# VME_buffers.net
KiCad netlist of a schematic drawn in Altium Designer
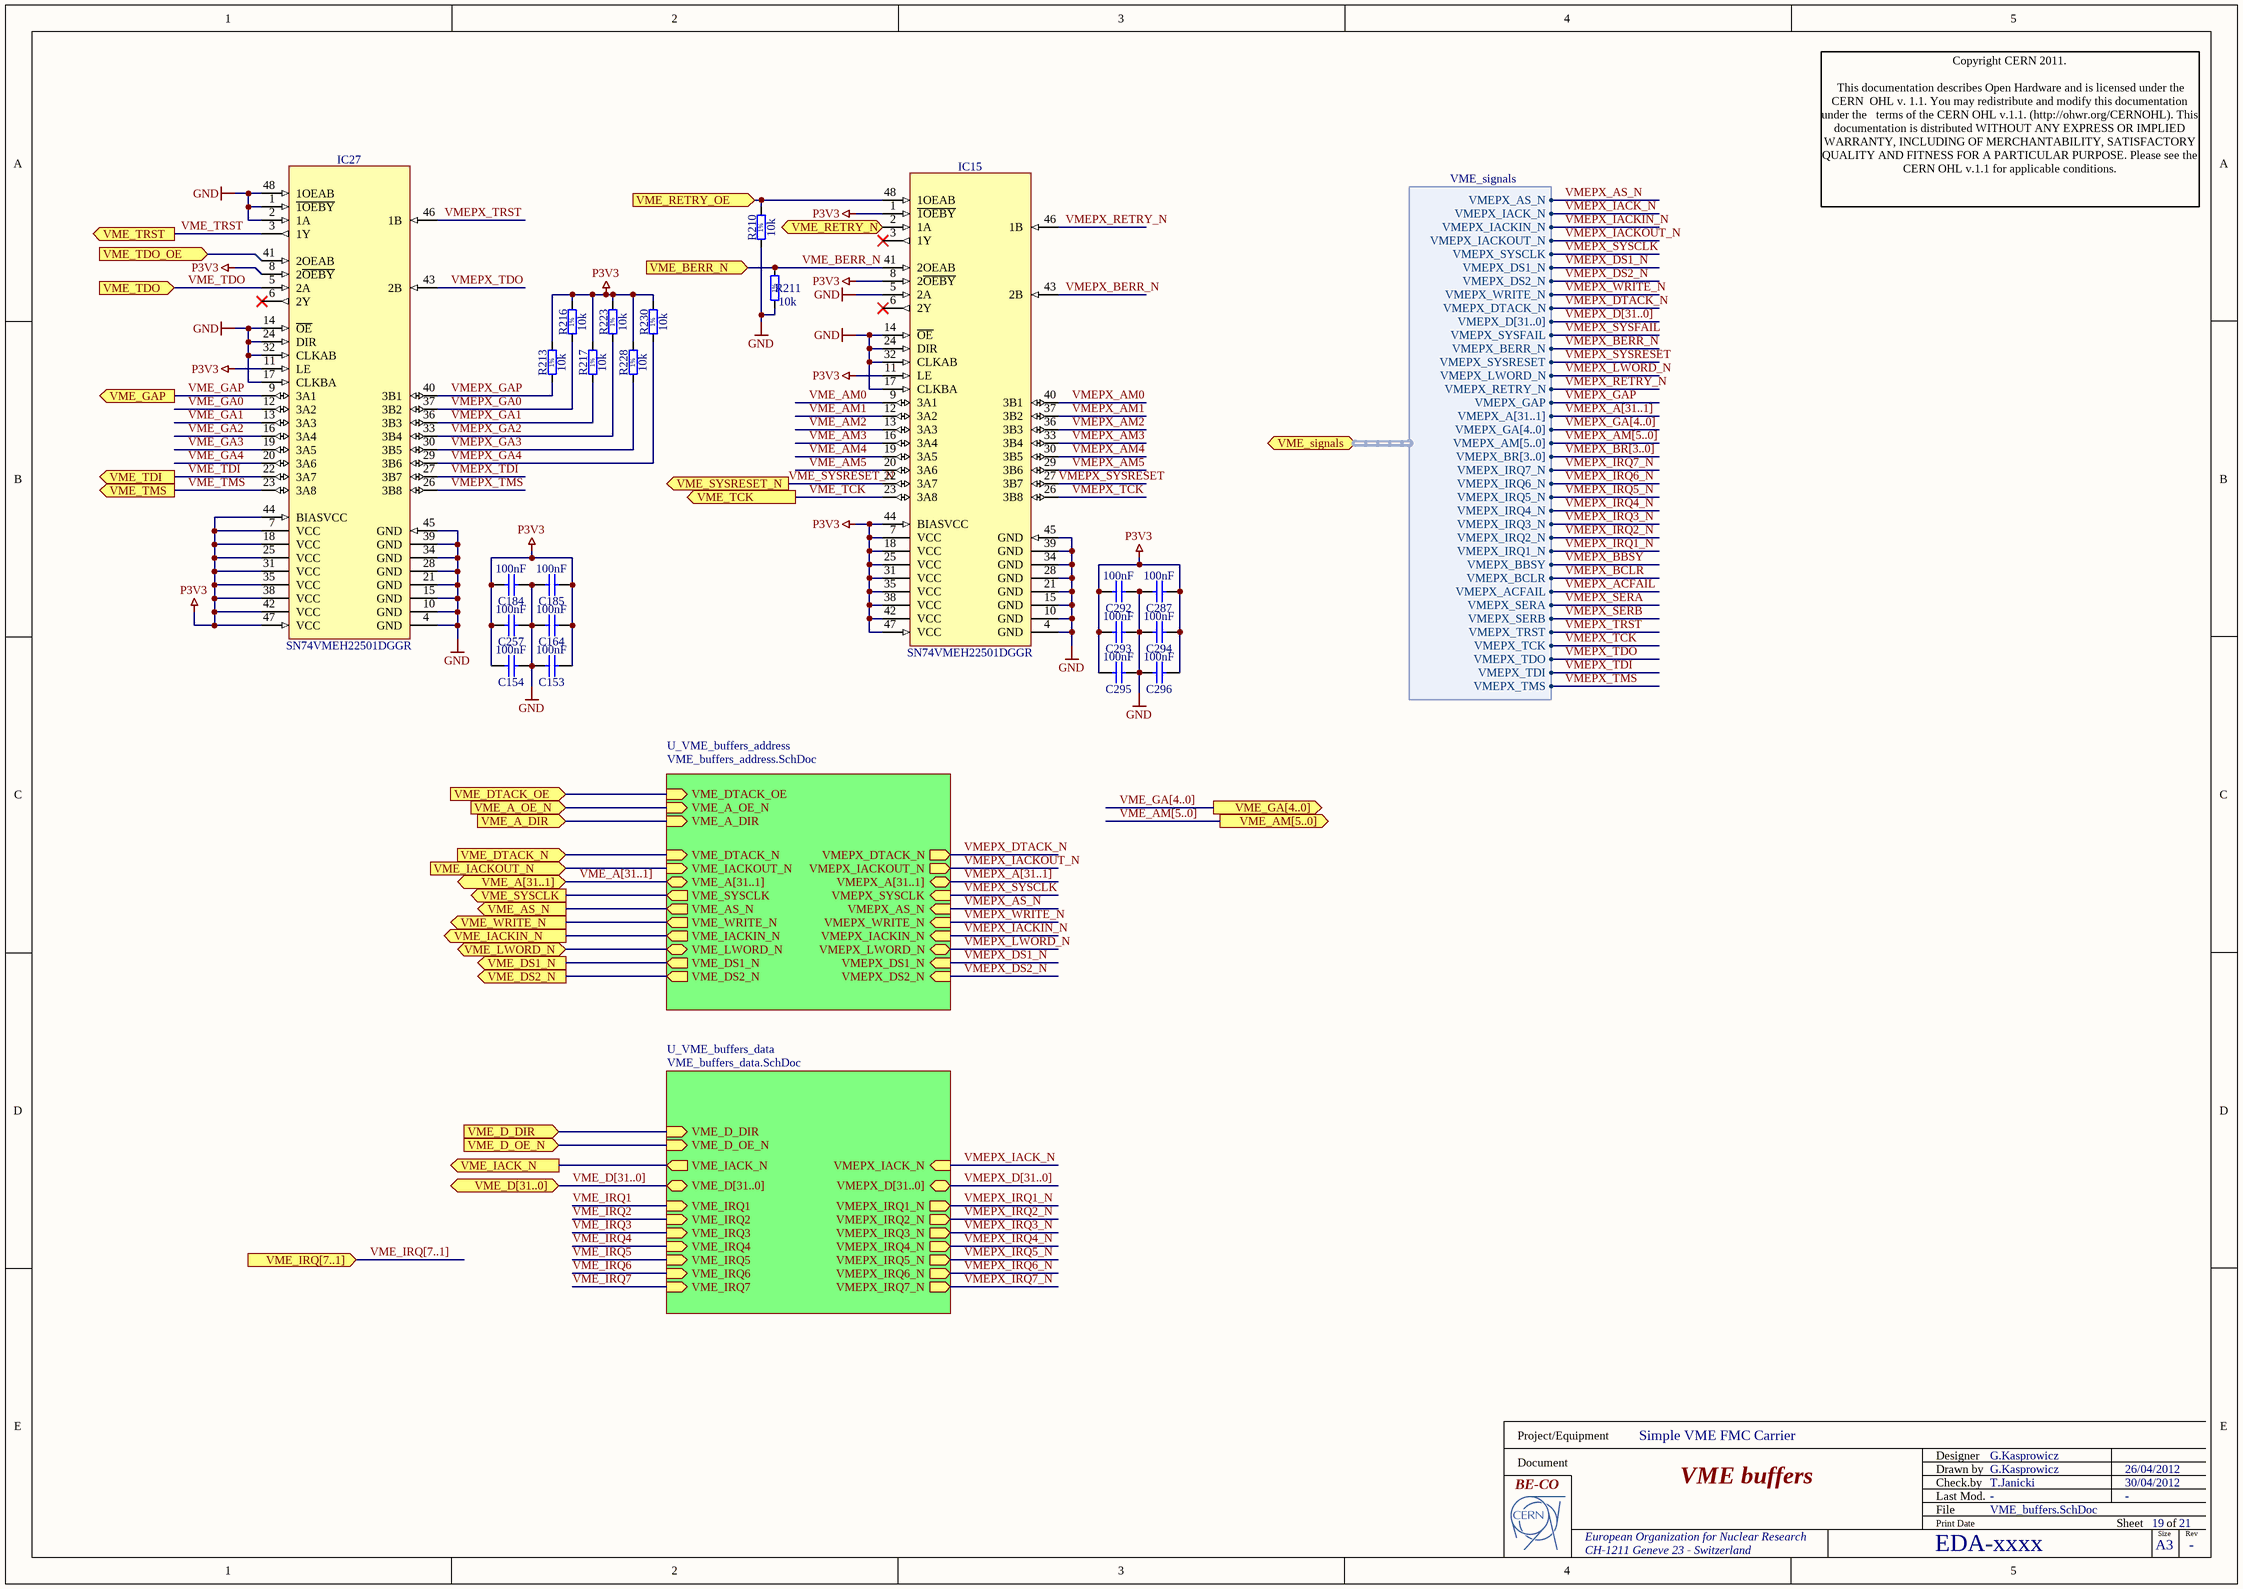
[diagram p0: VME_buffers.SchDoc]

(export (version "E")
  (design (tool "Eeschema 10.0.6"))
  (components
    (comp (ref "C153")
      (value "100nF")
      (footprint "CAPC1005X55N")
      (description "Non-polarised capacitor")
      (fields
        (field (name "PART NUMBER") "CC0402_100NF_16V_10%_X7R")
        (field (name "VOLTAGE") "16V")
        (field (name "AUTHOR") "CERN DEM JLC")
      )
      (libsource (lib "Capacitors") (part "Capacitor - non polarized"))
    )
    (comp (ref "C154")
      (value "100nF")
      (footprint "CAPC1005X55N")
      (description "Non-polarised capacitor")
      (fields
        (field (name "PART NUMBER") "CC0402_100NF_16V_10%_X7R")
        (field (name "VOLTAGE") "16V")
        (field (name "AUTHOR") "CERN DEM JLC")
      )
      (libsource (lib "Capacitors") (part "Capacitor - non polarized"))
    )
    (comp (ref "C164")
      (value "100nF")
      (footprint "CAPC1005X55N")
      (description "Non-polarised capacitor")
      (fields
        (field (name "PART NUMBER") "CC0402_100NF_16V_10%_X7R")
        (field (name "VOLTAGE") "16V")
        (field (name "AUTHOR") "CERN DEM JLC")
      )
      (libsource (lib "Capacitors") (part "Capacitor - non polarized"))
    )
    (comp (ref "C184")
      (value "100nF")
      (footprint "CAPC1005X55N")
      (description "Non-polarised capacitor")
      (fields
        (field (name "PART NUMBER") "CC0402_100NF_16V_10%_X7R")
        (field (name "VOLTAGE") "16V")
        (field (name "AUTHOR") "CERN DEM JLC")
      )
      (libsource (lib "Capacitors") (part "Capacitor - non polarized"))
    )
    (comp (ref "C185")
      (value "100nF")
      (footprint "CAPC1005X55N")
      (description "Non-polarised capacitor")
      (fields
        (field (name "PART NUMBER") "CC0402_100NF_16V_10%_X7R")
        (field (name "VOLTAGE") "16V")
        (field (name "AUTHOR") "CERN DEM JLC")
      )
      (libsource (lib "Capacitors") (part "Capacitor - non polarized"))
    )
    (comp (ref "C257")
      (value "100nF")
      (footprint "CAPC1005X55N")
      (description "Non-polarised capacitor")
      (fields
        (field (name "PART NUMBER") "CC0402_100NF_16V_10%_X7R")
        (field (name "VOLTAGE") "16V")
        (field (name "AUTHOR") "CERN DEM JLC")
      )
      (libsource (lib "Capacitors") (part "Capacitor - non polarized"))
    )
    (comp (ref "C287")
      (value "100nF")
      (footprint "CAPC1005X55N")
      (description "Non-polarised capacitor")
      (fields
        (field (name "PART NUMBER") "CC0402_100NF_16V_10%_X7R")
        (field (name "VOLTAGE") "16V")
        (field (name "AUTHOR") "CERN DEM JLC")
      )
      (libsource (lib "Capacitors") (part "Capacitor - non polarized"))
    )
    (comp (ref "C292")
      (value "100nF")
      (footprint "CAPC1005X55N")
      (description "Non-polarised capacitor")
      (fields
        (field (name "PART NUMBER") "CC0402_100NF_16V_10%_X7R")
        (field (name "VOLTAGE") "16V")
        (field (name "AUTHOR") "CERN DEM JLC")
      )
      (libsource (lib "Capacitors") (part "Capacitor - non polarized"))
    )
    (comp (ref "C293")
      (value "100nF")
      (footprint "CAPC1005X55N")
      (description "Non-polarised capacitor")
      (fields
        (field (name "PART NUMBER") "CC0402_100NF_16V_10%_X7R")
        (field (name "VOLTAGE") "16V")
        (field (name "AUTHOR") "CERN DEM JLC")
      )
      (libsource (lib "Capacitors") (part "Capacitor - non polarized"))
    )
    (comp (ref "C294")
      (value "100nF")
      (footprint "CAPC1005X55N")
      (description "Non-polarised capacitor")
      (fields
        (field (name "PART NUMBER") "CC0402_100NF_16V_10%_X7R")
        (field (name "VOLTAGE") "16V")
        (field (name "AUTHOR") "CERN DEM JLC")
      )
      (libsource (lib "Capacitors") (part "Capacitor - non polarized"))
    )
    (comp (ref "C295")
      (value "100nF")
      (footprint "CAPC1005X55N")
      (description "Non-polarised capacitor")
      (fields
        (field (name "PART NUMBER") "CC0402_100NF_16V_10%_X7R")
        (field (name "VOLTAGE") "16V")
        (field (name "AUTHOR") "CERN DEM JLC")
      )
      (libsource (lib "Capacitors") (part "Capacitor - non polarized"))
    )
    (comp (ref "C296")
      (value "100nF")
      (footprint "CAPC1005X55N")
      (description "Non-polarised capacitor")
      (fields
        (field (name "PART NUMBER") "CC0402_100NF_16V_10%_X7R")
        (field (name "VOLTAGE") "16V")
        (field (name "AUTHOR") "CERN DEM JLC")
      )
      (libsource (lib "Capacitors") (part "Capacitor - non polarized"))
    )
    (comp (ref "IC15")
      (value "SN74VMEH22501DGGR")
      (footprint "SOP50P810X120-48N")
      (description "8-Bit Universal Bus Transceiver and Two 1-Bit Bus Transceivers with 3-State Outputs")
      (fields (field (name "MANUFACTURER") "TEXAS INSTRUMENTS") (field (name "AUTHOR") "CERN DEM JLC"))
      (libsource (lib "ICs And Semiconductors") (part "74VMEH22501"))
    )
    (comp (ref "IC27")
      (value "SN74VMEH22501DGGR")
      (footprint "SOP50P810X120-48N")
      (description "8-Bit Universal Bus Transceiver and Two 1-Bit Bus Transceivers with 3-State Outputs")
      (fields (field (name "MANUFACTURER") "TEXAS INSTRUMENTS") (field (name "AUTHOR") "CERN DEM JLC"))
      (libsource (lib "ICs And Semiconductors") (part "74VMEH22501"))
    )
    (comp (ref "R210")
      (value "10k")
      (footprint "RESC1608X55N")
      (description "Resistor - 1%")
      (fields
        (field (name "PART NUMBER") "R0603_10K_1%_0.1W_100PPM")
        (field (name "POWER") "0.1W")
        (field (name "AUTHOR") "CERN DEM JLC")
      )
      (libsource (lib "Resistors") (part "Resistor - 1%"))
    )
    (comp (ref "R211")
      (value "10k")
      (footprint "RESC1608X55N")
      (description "Resistor - 1%")
      (fields
        (field (name "PART NUMBER") "R0603_10K_1%_0.1W_100PPM")
        (field (name "POWER") "0.1W")
        (field (name "AUTHOR") "CERN DEM JLC")
      )
      (libsource (lib "Resistors") (part "Resistor - 1%"))
    )
    (comp (ref "R213")
      (value "10k")
      (footprint "RESC1608X55N")
      (description "Resistor - 1%")
      (fields
        (field (name "PART NUMBER") "R0603_10K_1%_0.1W_100PPM")
        (field (name "POWER") "0.1W")
        (field (name "AUTHOR") "CERN DEM JLC")
      )
      (libsource (lib "Resistors") (part "Resistor - 1%"))
    )
    (comp (ref "R216")
      (value "10k")
      (footprint "RESC1608X55N")
      (description "Resistor - 1%")
      (fields
        (field (name "PART NUMBER") "R0603_10K_1%_0.1W_100PPM")
        (field (name "POWER") "0.1W")
        (field (name "AUTHOR") "CERN DEM JLC")
      )
      (libsource (lib "Resistors") (part "Resistor - 1%"))
    )
    (comp (ref "R217")
      (value "10k")
      (footprint "RESC1608X55N")
      (description "Resistor - 1%")
      (fields
        (field (name "PART NUMBER") "R0603_10K_1%_0.1W_100PPM")
        (field (name "POWER") "0.1W")
        (field (name "AUTHOR") "CERN DEM JLC")
      )
      (libsource (lib "Resistors") (part "Resistor - 1%"))
    )
    (comp (ref "R223")
      (value "10k")
      (footprint "RESC1608X55N")
      (description "Resistor - 1%")
      (fields
        (field (name "PART NUMBER") "R0603_10K_1%_0.1W_100PPM")
        (field (name "POWER") "0.1W")
        (field (name "AUTHOR") "CERN DEM JLC")
      )
      (libsource (lib "Resistors") (part "Resistor - 1%"))
    )
    (comp (ref "R228")
      (value "10k")
      (footprint "RESC1608X55N")
      (description "Resistor - 1%")
      (fields
        (field (name "PART NUMBER") "R0603_10K_1%_0.1W_100PPM")
        (field (name "POWER") "0.1W")
        (field (name "AUTHOR") "CERN DEM JLC")
      )
      (libsource (lib "Resistors") (part "Resistor - 1%"))
    )
    (comp (ref "R230")
      (value "10k")
      (footprint "RESC1608X55N")
      (description "Resistor - 1%")
      (fields
        (field (name "PART NUMBER") "R0603_10K_1%_0.1W_100PPM")
        (field (name "POWER") "0.1W")
        (field (name "AUTHOR") "CERN DEM JLC")
      )
      (libsource (lib "Resistors") (part "Resistor - 1%"))
    )
  )
  (nets
    (net (code "129") (name "/VMEPX_AM0") (class "Default")
      (node (ref "IC15") (pin "40") (pinfunction "3B1_40") (pintype "bidirectional"))
    )
    (net (code "130") (name "/VMEPX_AM1") (class "Default")
      (node (ref "IC15") (pin "37") (pinfunction "3B2_37") (pintype "bidirectional"))
    )
    (net (code "131") (name "/VMEPX_AM2") (class "Default")
      (node (ref "IC15") (pin "36") (pinfunction "3B3_36") (pintype "bidirectional"))
    )
    (net (code "132") (name "/VMEPX_AM3") (class "Default")
      (node (ref "IC15") (pin "33") (pinfunction "3B4_33") (pintype "bidirectional"))
    )
    (net (code "133") (name "/VMEPX_AM4") (class "Default")
      (node (ref "IC15") (pin "30") (pinfunction "3B5_30") (pintype "bidirectional"))
    )
    (net (code "134") (name "/VMEPX_AM5") (class "Default")
      (node (ref "IC15") (pin "29") (pinfunction "3B6_29") (pintype "bidirectional"))
    )
    (net (code "140") (name "/VMEPX_BERR_N") (class "Default")
      (node (ref "IC15") (pin "43") (pinfunction "2B_43") (pintype "input"))
    )
    (net (code "145") (name "/VMEPX_GA0") (class "Default")
      (node (ref "IC27") (pin "37") (pinfunction "3B2_37") (pintype "bidirectional"))
      (node (ref "R216") (pin "1") (pinfunction "1_1") (pintype "passive"))
    )
    (net (code "146") (name "/VMEPX_GA1") (class "Default")
      (node (ref "IC27") (pin "36") (pinfunction "3B3_36") (pintype "bidirectional"))
      (node (ref "R217") (pin "1") (pinfunction "1_1") (pintype "passive"))
    )
    (net (code "147") (name "/VMEPX_GA2") (class "Default")
      (node (ref "IC27") (pin "33") (pinfunction "3B4_33") (pintype "bidirectional"))
      (node (ref "R223") (pin "1") (pinfunction "1_1") (pintype "passive"))
    )
    (net (code "148") (name "/VMEPX_GA3") (class "Default")
      (node (ref "IC27") (pin "30") (pinfunction "3B5_30") (pintype "bidirectional"))
      (node (ref "R228") (pin "1") (pinfunction "1_1") (pintype "passive"))
    )
    (net (code "149") (name "/VMEPX_GA4") (class "Default")
      (node (ref "IC27") (pin "29") (pinfunction "3B6_29") (pintype "bidirectional"))
      (node (ref "R230") (pin "1") (pinfunction "1_1") (pintype "passive"))
    )
    (net (code "150") (name "/VMEPX_GAP") (class "Default")
      (node (ref "IC27") (pin "40") (pinfunction "3B1_40") (pintype "bidirectional"))
      (node (ref "R213") (pin "1") (pinfunction "1_1") (pintype "passive"))
    )
    (net (code "163") (name "/VMEPX_RETRY_N") (class "Default")
      (node (ref "IC15") (pin "46") (pinfunction "1B_46") (pintype "input"))
    )
    (net (code "168") (name "/VMEPX_SYSRESET") (class "Default")
      (node (ref "IC15") (pin "27") (pinfunction "3B7_27") (pintype "bidirectional"))
    )
    (net (code "169") (name "/VMEPX_TCK") (class "Default")
      (node (ref "IC15") (pin "26") (pinfunction "3B8_26") (pintype "bidirectional"))
    )
    (net (code "170") (name "/VMEPX_TDI") (class "Default")
      (node (ref "IC27") (pin "27") (pinfunction "3B7_27") (pintype "bidirectional"))
    )
    (net (code "171") (name "/VMEPX_TDO") (class "Default")
      (node (ref "IC27") (pin "43") (pinfunction "2B_43") (pintype "input"))
    )
    (net (code "172") (name "/VMEPX_TMS") (class "Default")
      (node (ref "IC27") (pin "26") (pinfunction "3B8_26") (pintype "bidirectional"))
    )
    (net (code "173") (name "/VMEPX_TRST") (class "Default")
      (node (ref "IC27") (pin "46") (pinfunction "1B_46") (pintype "input"))
    )
    (net (code "175") (name "/VME_AM0") (class "Default")
      (node (ref "IC15") (pin "9") (pinfunction "3A1_9") (pintype "bidirectional"))
    )
    (net (code "176") (name "/VME_AM1") (class "Default")
      (node (ref "IC15") (pin "12") (pinfunction "3A2_12") (pintype "bidirectional"))
    )
    (net (code "177") (name "/VME_AM2") (class "Default")
      (node (ref "IC15") (pin "13") (pinfunction "3A3_13") (pintype "bidirectional"))
    )
    (net (code "178") (name "/VME_AM3") (class "Default")
      (node (ref "IC15") (pin "16") (pinfunction "3A4_16") (pintype "bidirectional"))
    )
    (net (code "179") (name "/VME_AM4") (class "Default")
      (node (ref "IC15") (pin "19") (pinfunction "3A5_19") (pintype "bidirectional"))
    )
    (net (code "180") (name "/VME_AM5") (class "Default")
      (node (ref "IC15") (pin "20") (pinfunction "3A6_20") (pintype "bidirectional"))
    )
    (net (code "186") (name "/VME_BERR_N") (class "Default")
      (node (ref "IC15") (pin "41") (pinfunction "2OEAB_41") (pintype "input"))
      (node (ref "R211") (pin "2") (pinfunction "2_2") (pintype "passive"))
    )
    (net (code "194") (name "/VME_GA0") (class "Default")
      (node (ref "IC27") (pin "12") (pinfunction "3A2_12") (pintype "bidirectional"))
    )
    (net (code "195") (name "/VME_GA1") (class "Default")
      (node (ref "IC27") (pin "13") (pinfunction "3A3_13") (pintype "bidirectional"))
    )
    (net (code "196") (name "/VME_GA2") (class "Default")
      (node (ref "IC27") (pin "16") (pinfunction "3A4_16") (pintype "bidirectional"))
    )
    (net (code "197") (name "/VME_GA3") (class "Default")
      (node (ref "IC27") (pin "19") (pinfunction "3A5_19") (pintype "bidirectional"))
    )
    (net (code "198") (name "/VME_GA4") (class "Default")
      (node (ref "IC27") (pin "20") (pinfunction "3A6_20") (pintype "bidirectional"))
    )
    (net (code "199") (name "/VME_GAP") (class "Default")
      (node (ref "IC27") (pin "9") (pinfunction "3A1_9") (pintype "bidirectional"))
    )
    (net (code "213") (name "/VME_RETRY_N") (class "Default")
      (node (ref "IC15") (pin "2") (pinfunction "1A_2") (pintype "input"))
    )
    (net (code "214") (name "/VME_RETRY_OE") (class "Default")
      (node (ref "IC15") (pin "48") (pinfunction "1OEAB_48") (pintype "input"))
      (node (ref "R210") (pin "2") (pinfunction "2_2") (pintype "passive"))
    )
    (net (code "216") (name "/VME_SYSRESET_N") (class "Default")
      (node (ref "IC15") (pin "22") (pinfunction "3A7_22") (pintype "bidirectional"))
    )
    (net (code "217") (name "/VME_TCK") (class "Default")
      (node (ref "IC15") (pin "23") (pinfunction "3A8_23") (pintype "bidirectional"))
    )
    (net (code "218") (name "/VME_TDI") (class "Default")
      (node (ref "IC27") (pin "22") (pinfunction "3A7_22") (pintype "bidirectional"))
    )
    (net (code "219") (name "/VME_TDO") (class "Default")
      (node (ref "IC27") (pin "5") (pinfunction "2A_5") (pintype "input"))
    )
    (net (code "220") (name "/VME_TDO_OE") (class "Default")
      (node (ref "IC27") (pin "41") (pinfunction "2OEAB_41") (pintype "input"))
    )
    (net (code "221") (name "/VME_TMS") (class "Default")
      (node (ref "IC27") (pin "23") (pinfunction "3A8_23") (pintype "bidirectional"))
    )
    (net (code "222") (name "/VME_TRST") (class "Default")
      (node (ref "IC27") (pin "3") (pinfunction "1Y_3") (pintype "output"))
    )
    (net (code "226") (name "GND") (class "Default")
      (node (ref "C153") (pin "2") (pinfunction "2_2") (pintype "passive"))
      (node (ref "C154") (pin "1") (pinfunction "1_1") (pintype "passive"))
      (node (ref "C164") (pin "2") (pinfunction "2_2") (pintype "passive"))
      (node (ref "C184") (pin "1") (pinfunction "1_1") (pintype "passive"))
      (node (ref "C185") (pin "2") (pinfunction "2_2") (pintype "passive"))
      (node (ref "C257") (pin "1") (pinfunction "1_1") (pintype "passive"))
      (node (ref "C287") (pin "2") (pinfunction "2_2") (pintype "passive"))
      (node (ref "C292") (pin "1") (pinfunction "1_1") (pintype "passive"))
      (node (ref "C293") (pin "1") (pinfunction "1_1") (pintype "passive"))
      (node (ref "C294") (pin "2") (pinfunction "2_2") (pintype "passive"))
      (node (ref "C295") (pin "1") (pinfunction "1_1") (pintype "passive"))
      (node (ref "C296") (pin "2") (pinfunction "2_2") (pintype "passive"))
      (node (ref "IC15") (pin "10") (pinfunction "GND_10") (pintype "power_in"))
      (node (ref "IC15") (pin "14") (pinfunction "~{OE}_14") (pintype "input"))
      (node (ref "IC15") (pin "15") (pinfunction "GND_15") (pintype "power_in"))
      (node (ref "IC15") (pin "17") (pinfunction "CLKBA_17") (pintype "input"))
      (node (ref "IC15") (pin "21") (pinfunction "GND_21") (pintype "power_in"))
      (node (ref "IC15") (pin "24") (pinfunction "DIR_24") (pintype "input"))
      (node (ref "IC15") (pin "28") (pinfunction "GND_28") (pintype "power_in"))
      (node (ref "IC15") (pin "32") (pinfunction "CLKAB_32") (pintype "input"))
      (node (ref "IC15") (pin "34") (pinfunction "GND_34") (pintype "power_in"))
      (node (ref "IC15") (pin "39") (pinfunction "GND_39") (pintype "power_in"))
      (node (ref "IC15") (pin "4") (pinfunction "GND_4") (pintype "power_in"))
      (node (ref "IC15") (pin "45") (pinfunction "GND_45") (pintype "input"))
      (node (ref "IC15") (pin "5") (pinfunction "2A_5") (pintype "input"))
      (node (ref "IC27") (pin "1") (pinfunction "~{1OEBY}_1") (pintype "input"))
      (node (ref "IC27") (pin "10") (pinfunction "GND_10") (pintype "power_in"))
      (node (ref "IC27") (pin "14") (pinfunction "~{OE}_14") (pintype "input"))
      (node (ref "IC27") (pin "15") (pinfunction "GND_15") (pintype "power_in"))
      (node (ref "IC27") (pin "17") (pinfunction "CLKBA_17") (pintype "input"))
      (node (ref "IC27") (pin "2") (pinfunction "1A_2") (pintype "input"))
      (node (ref "IC27") (pin "21") (pinfunction "GND_21") (pintype "power_in"))
      (node (ref "IC27") (pin "24") (pinfunction "DIR_24") (pintype "input"))
      (node (ref "IC27") (pin "28") (pinfunction "GND_28") (pintype "power_in"))
      (node (ref "IC27") (pin "32") (pinfunction "CLKAB_32") (pintype "input"))
      (node (ref "IC27") (pin "34") (pinfunction "GND_34") (pintype "power_in"))
      (node (ref "IC27") (pin "39") (pinfunction "GND_39") (pintype "power_in"))
      (node (ref "IC27") (pin "4") (pinfunction "GND_4") (pintype "power_in"))
      (node (ref "IC27") (pin "45") (pinfunction "GND_45") (pintype "input"))
      (node (ref "IC27") (pin "48") (pinfunction "1OEAB_48") (pintype "input"))
      (node (ref "R210") (pin "1") (pinfunction "1_1") (pintype "passive"))
      (node (ref "R211") (pin "1") (pinfunction "1_1") (pintype "passive"))
    )
    (net (code "227") (name "P3V3") (class "Default")
      (node (ref "C153") (pin "1") (pinfunction "1_1") (pintype "passive"))
      (node (ref "C154") (pin "2") (pinfunction "2_2") (pintype "passive"))
      (node (ref "C164") (pin "1") (pinfunction "1_1") (pintype "passive"))
      (node (ref "C184") (pin "2") (pinfunction "2_2") (pintype "passive"))
      (node (ref "C185") (pin "1") (pinfunction "1_1") (pintype "passive"))
      (node (ref "C257") (pin "2") (pinfunction "2_2") (pintype "passive"))
      (node (ref "C287") (pin "1") (pinfunction "1_1") (pintype "passive"))
      (node (ref "C292") (pin "2") (pinfunction "2_2") (pintype "passive"))
      (node (ref "C293") (pin "2") (pinfunction "2_2") (pintype "passive"))
      (node (ref "C294") (pin "1") (pinfunction "1_1") (pintype "passive"))
      (node (ref "C295") (pin "2") (pinfunction "2_2") (pintype "passive"))
      (node (ref "C296") (pin "1") (pinfunction "1_1") (pintype "passive"))
      (node (ref "IC15") (pin "1") (pinfunction "~{1OEBY}_1") (pintype "input"))
      (node (ref "IC15") (pin "11") (pinfunction "LE_11") (pintype "input"))
      (node (ref "IC15") (pin "18") (pinfunction "VCC_18") (pintype "power_in"))
      (node (ref "IC15") (pin "25") (pinfunction "VCC_25") (pintype "power_in"))
      (node (ref "IC15") (pin "31") (pinfunction "VCC_31") (pintype "power_in"))
      (node (ref "IC15") (pin "35") (pinfunction "VCC_35") (pintype "power_in"))
      (node (ref "IC15") (pin "38") (pinfunction "VCC_38") (pintype "power_in"))
      (node (ref "IC15") (pin "42") (pinfunction "VCC_42") (pintype "power_in"))
      (node (ref "IC15") (pin "44") (pinfunction "BIASVCC_44") (pintype "input"))
      (node (ref "IC15") (pin "47") (pinfunction "VCC_47") (pintype "input"))
      (node (ref "IC15") (pin "7") (pinfunction "VCC_7") (pintype "power_in"))
      (node (ref "IC15") (pin "8") (pinfunction "2~{OEBY}_8") (pintype "input"))
      (node (ref "IC27") (pin "11") (pinfunction "LE_11") (pintype "input"))
      (node (ref "IC27") (pin "18") (pinfunction "VCC_18") (pintype "power_in"))
      (node (ref "IC27") (pin "25") (pinfunction "VCC_25") (pintype "power_in"))
      (node (ref "IC27") (pin "31") (pinfunction "VCC_31") (pintype "power_in"))
      (node (ref "IC27") (pin "35") (pinfunction "VCC_35") (pintype "power_in"))
      (node (ref "IC27") (pin "38") (pinfunction "VCC_38") (pintype "power_in"))
      (node (ref "IC27") (pin "42") (pinfunction "VCC_42") (pintype "power_in"))
      (node (ref "IC27") (pin "44") (pinfunction "BIASVCC_44") (pintype "input"))
      (node (ref "IC27") (pin "47") (pinfunction "VCC_47") (pintype "input"))
      (node (ref "IC27") (pin "7") (pinfunction "VCC_7") (pintype "power_in"))
      (node (ref "IC27") (pin "8") (pinfunction "2~{OEBY}_8") (pintype "input"))
      (node (ref "R213") (pin "2") (pinfunction "2_2") (pintype "passive"))
      (node (ref "R216") (pin "2") (pinfunction "2_2") (pintype "passive"))
      (node (ref "R217") (pin "2") (pinfunction "2_2") (pintype "passive"))
      (node (ref "R223") (pin "2") (pinfunction "2_2") (pintype "passive"))
      (node (ref "R228") (pin "2") (pinfunction "2_2") (pintype "passive"))
      (node (ref "R230") (pin "2") (pinfunction "2_2") (pintype "passive"))
    )
    (net (code "228") (name "unconnected-(IC15-1Y-Pad3)") (class "Default")
      (node (ref "IC15") (pin "3") (pinfunction "1Y_3") (pintype "output+no_connect"))
    )
    (net (code "229") (name "unconnected-(IC15-2Y-Pad6)") (class "Default")
      (node (ref "IC15") (pin "6") (pinfunction "2Y_6") (pintype "output+no_connect"))
    )
    (net (code "230") (name "unconnected-(IC27-2Y-Pad6)") (class "Default")
      (node (ref "IC27") (pin "6") (pinfunction "2Y_6") (pintype "output+no_connect"))
    )
  )
)
